# ui_board.net
KiCad netlist of a schematic drawn in EAGLE
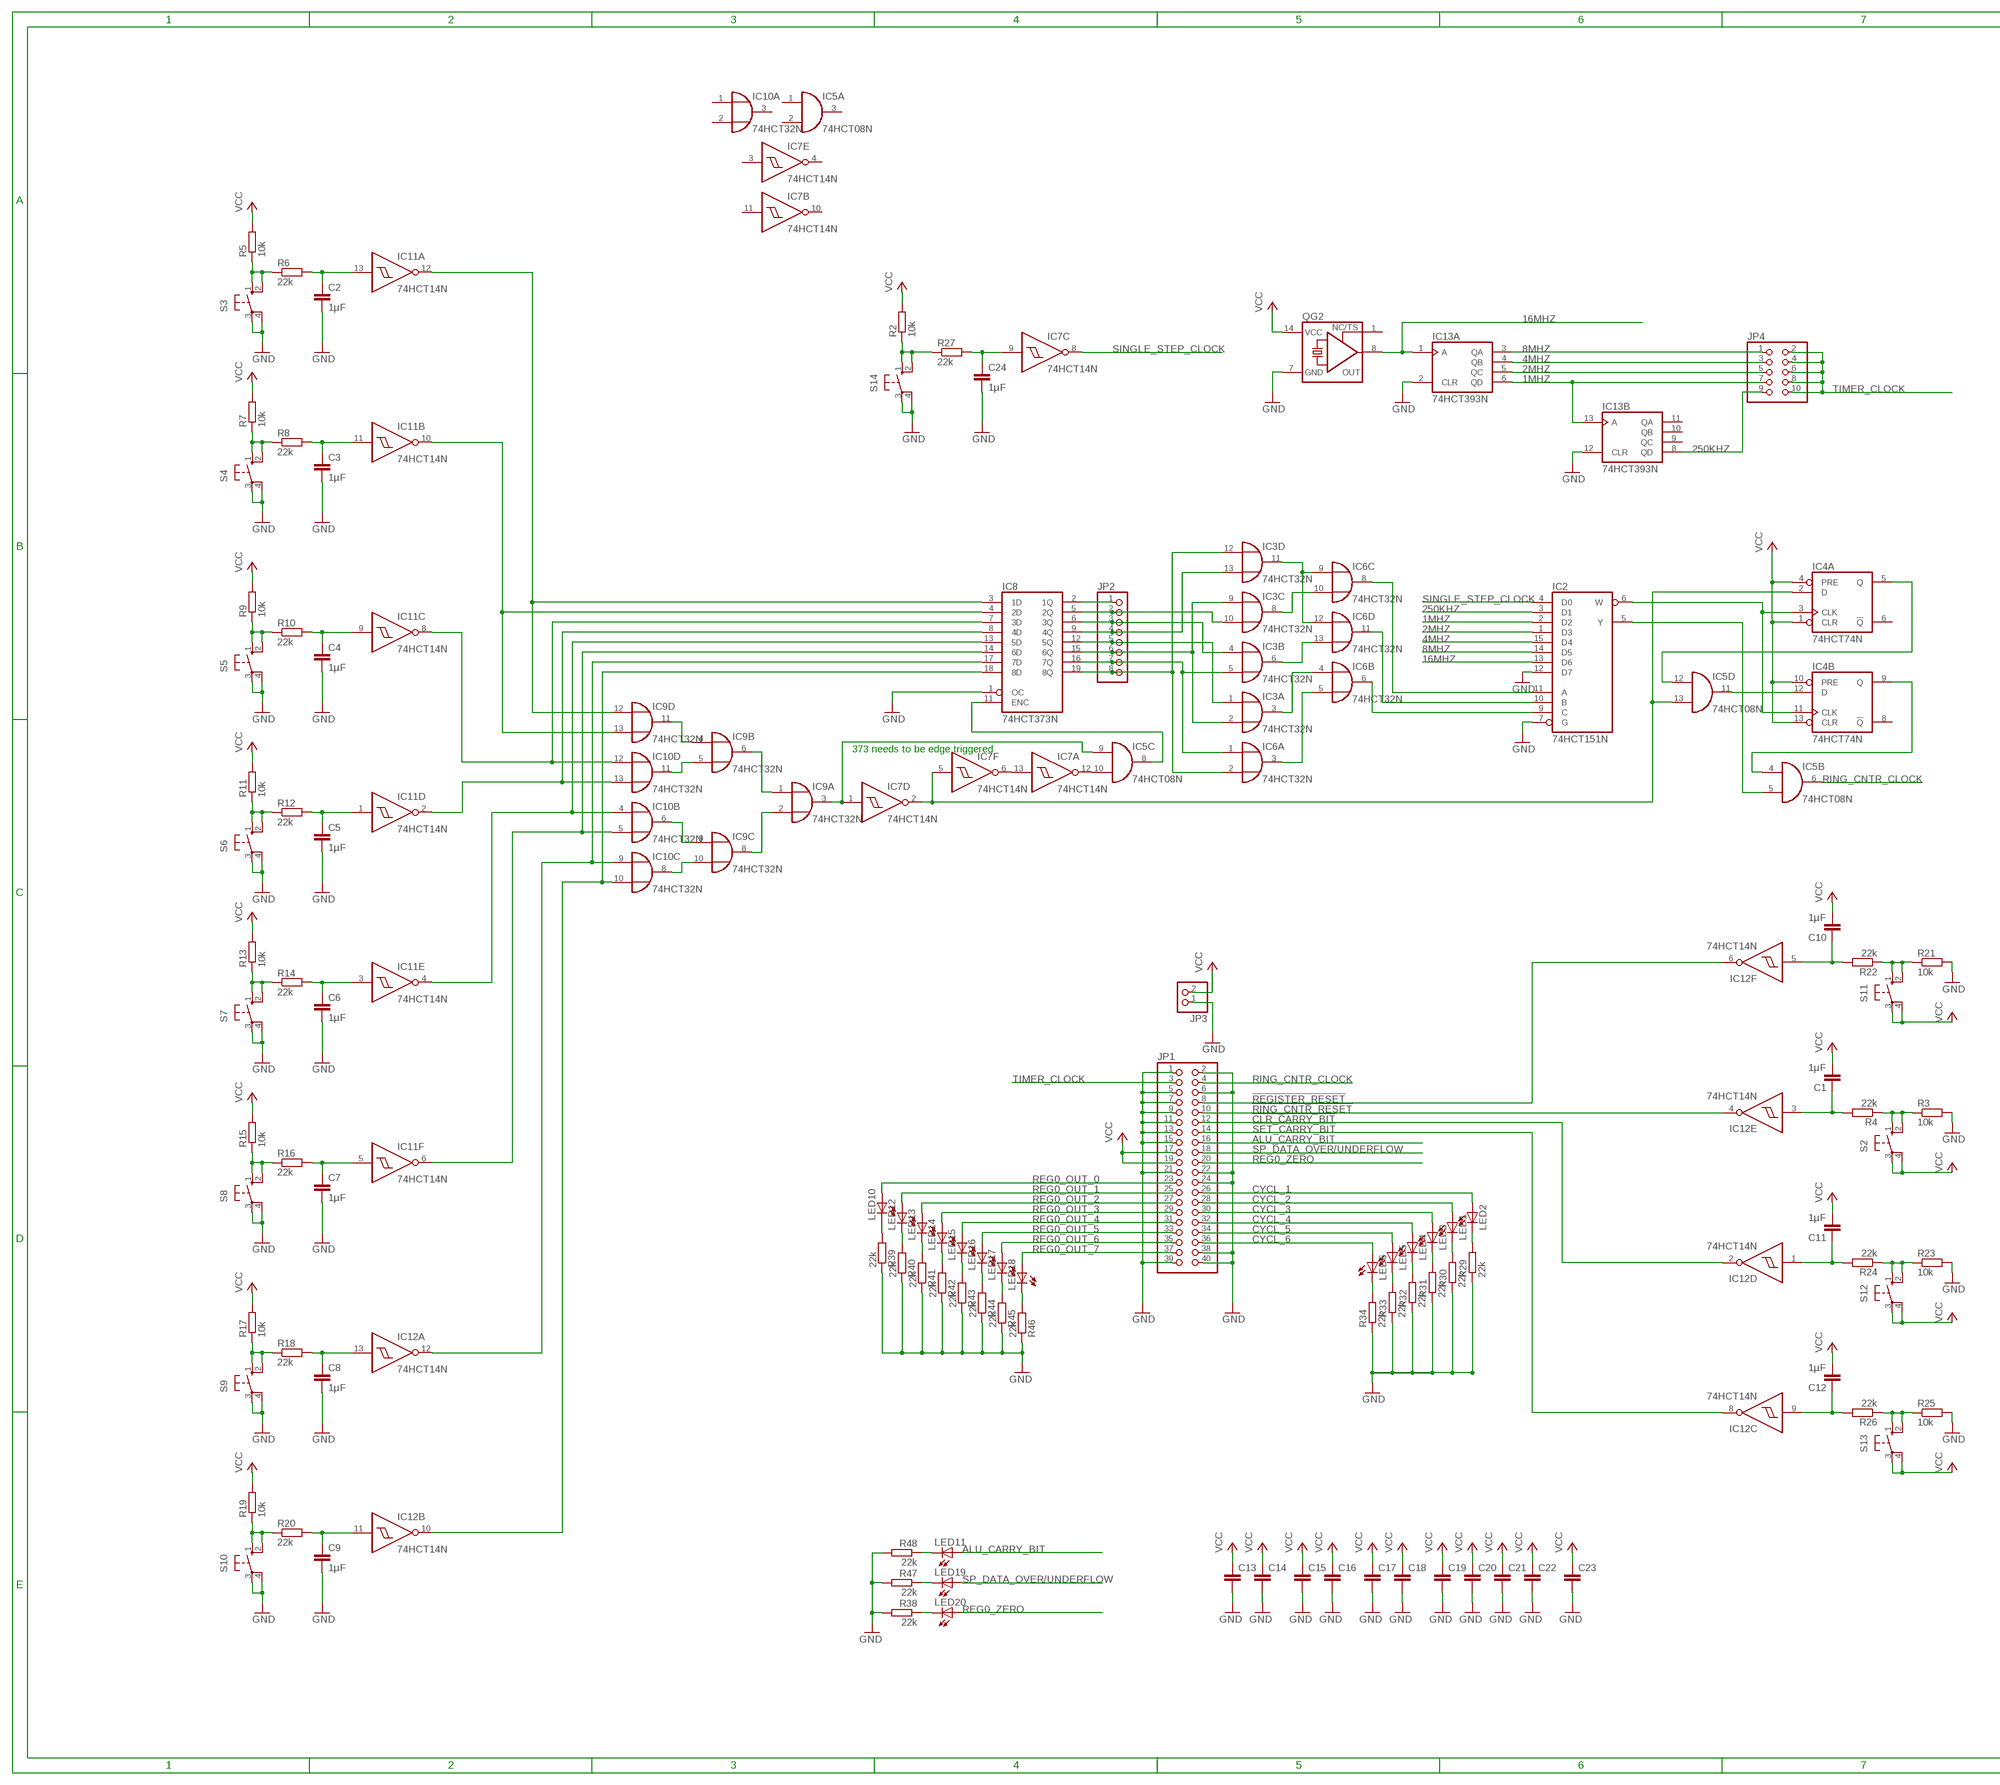
[diagram p0: schematic, sheet 1, part 1 of 2]
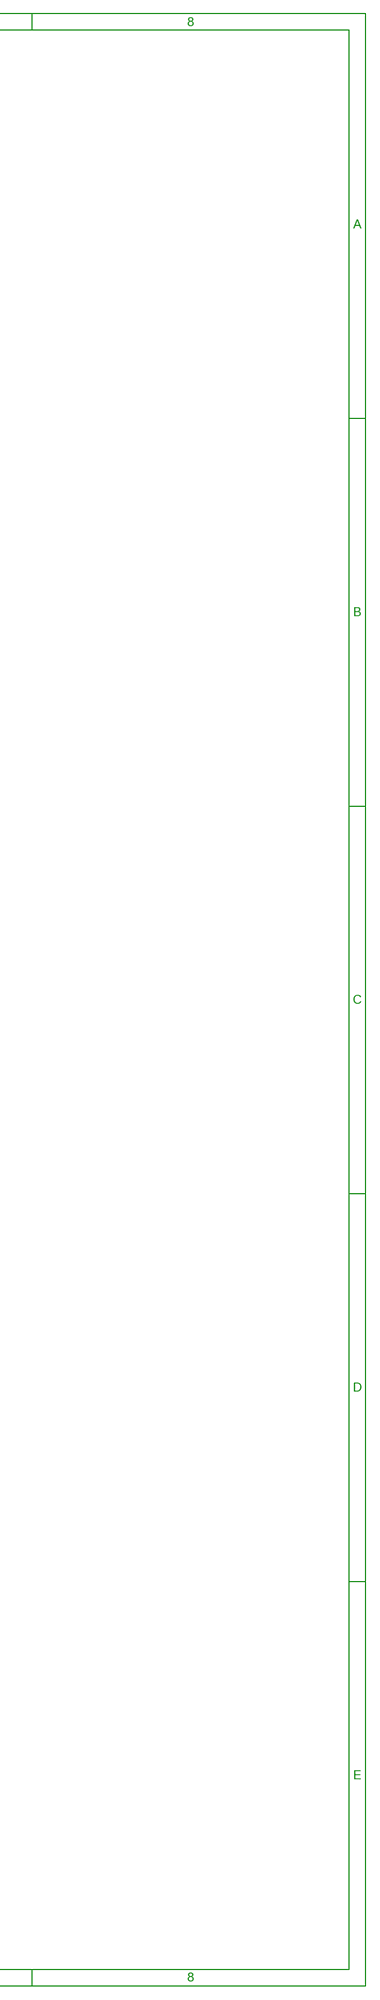
[diagram p1: schematic, sheet 1, part 2 of 2]

(export (version "E")
  (design (tool "Eeschema 10.0.6"))
  (components
    (comp (ref "C1")
      (value "1µF")
      (footprint "eagle-import:C025-024X044")
      (libsource (lib "eagle-import") (part "C-EU025-024X044"))
    )
    (comp (ref "C2")
      (value "1µF")
      (footprint "eagle-import:C025-024X044")
      (libsource (lib "eagle-import") (part "C-EU025-024X044"))
    )
    (comp (ref "C3")
      (value "1µF")
      (footprint "eagle-import:C025-024X044")
      (libsource (lib "eagle-import") (part "C-EU025-024X044"))
    )
    (comp (ref "C4")
      (value "1µF")
      (footprint "eagle-import:C025-024X044")
      (libsource (lib "eagle-import") (part "C-EU025-024X044"))
    )
    (comp (ref "C5")
      (value "1µF")
      (footprint "eagle-import:C025-024X044")
      (libsource (lib "eagle-import") (part "C-EU025-024X044"))
    )
    (comp (ref "C6")
      (value "1µF")
      (footprint "eagle-import:C025-024X044")
      (libsource (lib "eagle-import") (part "C-EU025-024X044"))
    )
    (comp (ref "C7")
      (value "1µF")
      (footprint "eagle-import:C025-024X044")
      (libsource (lib "eagle-import") (part "C-EU025-024X044"))
    )
    (comp (ref "C8")
      (value "1µF")
      (footprint "eagle-import:C025-024X044")
      (libsource (lib "eagle-import") (part "C-EU025-024X044"))
    )
    (comp (ref "C9")
      (value "1µF")
      (footprint "eagle-import:C025-024X044")
      (libsource (lib "eagle-import") (part "C-EU025-024X044"))
    )
    (comp (ref "C10")
      (value "1µF")
      (footprint "eagle-import:C025-024X044")
      (libsource (lib "eagle-import") (part "C-EU025-024X044"))
    )
    (comp (ref "C11")
      (value "1µF")
      (footprint "eagle-import:C025-024X044")
      (libsource (lib "eagle-import") (part "C-EU025-024X044"))
    )
    (comp (ref "C12")
      (value "1µF")
      (footprint "eagle-import:C025-024X044")
      (libsource (lib "eagle-import") (part "C-EU025-024X044"))
    )
    (comp (ref "C13")
      (value "C-EUC1206")
      (footprint "eagle-import:C1206")
      (libsource (lib "eagle-import") (part "C-EUC1206"))
    )
    (comp (ref "C14")
      (value "C-EUC1206")
      (footprint "eagle-import:C1206")
      (libsource (lib "eagle-import") (part "C-EUC1206"))
    )
    (comp (ref "C15")
      (value "C-EUC1206")
      (footprint "eagle-import:C1206")
      (libsource (lib "eagle-import") (part "C-EUC1206"))
    )
    (comp (ref "C16")
      (value "C-EUC1206")
      (footprint "eagle-import:C1206")
      (libsource (lib "eagle-import") (part "C-EUC1206"))
    )
    (comp (ref "C17")
      (value "C-EUC1206")
      (footprint "eagle-import:C1206")
      (libsource (lib "eagle-import") (part "C-EUC1206"))
    )
    (comp (ref "C18")
      (value "C-EUC1206")
      (footprint "eagle-import:C1206")
      (libsource (lib "eagle-import") (part "C-EUC1206"))
    )
    (comp (ref "C19")
      (value "C-EUC1206")
      (footprint "eagle-import:C1206")
      (libsource (lib "eagle-import") (part "C-EUC1206"))
    )
    (comp (ref "C20")
      (value "C-EUC1206")
      (footprint "eagle-import:C1206")
      (libsource (lib "eagle-import") (part "C-EUC1206"))
    )
    (comp (ref "C21")
      (value "C-EUC1206")
      (footprint "eagle-import:C1206")
      (libsource (lib "eagle-import") (part "C-EUC1206"))
    )
    (comp (ref "C22")
      (value "C-EUC1206")
      (footprint "eagle-import:C1206")
      (libsource (lib "eagle-import") (part "C-EUC1206"))
    )
    (comp (ref "C23")
      (value "C-EUC1206")
      (footprint "eagle-import:C1206")
      (libsource (lib "eagle-import") (part "C-EUC1206"))
    )
    (comp (ref "C24")
      (value "1µF")
      (footprint "eagle-import:C025-024X044")
      (libsource (lib "eagle-import") (part "C-EU025-024X044"))
    )
    (comp (ref "IC2")
      (value "74HCT151N")
      (footprint "eagle-import:DIL16")
      (libsource (lib "eagle-import") (part "74151NHCT"))
    )
    (comp (ref "IC3")
      (value "74HCT32N")
      (footprint "eagle-import:DIL14")
      (libsource (lib "eagle-import") (part "7432NHCT"))
    )
    (comp (ref "IC4")
      (value "74HCT74N")
      (footprint "eagle-import:DIL14")
      (libsource (lib "eagle-import") (part "7474NHCT"))
    )
    (comp (ref "IC5")
      (value "74HCT08N")
      (footprint "eagle-import:DIL14")
      (libsource (lib "eagle-import") (part "7408NHCT"))
    )
    (comp (ref "IC6")
      (value "74HCT32N")
      (footprint "eagle-import:DIL14")
      (libsource (lib "eagle-import") (part "7432NHCT"))
    )
    (comp (ref "IC7")
      (value "74HCT14N")
      (footprint "eagle-import:DIL14")
      (libsource (lib "eagle-import") (part "7414NHCT"))
    )
    (comp (ref "IC8")
      (value "74HCT373N")
      (footprint "eagle-import:DIL20")
      (libsource (lib "eagle-import") (part "74373NHCT"))
    )
    (comp (ref "IC9")
      (value "74HCT32N")
      (footprint "eagle-import:DIL14")
      (libsource (lib "eagle-import") (part "7432NHCT"))
    )
    (comp (ref "IC10")
      (value "74HCT32N")
      (footprint "eagle-import:DIL14")
      (libsource (lib "eagle-import") (part "7432NHCT"))
    )
    (comp (ref "IC11")
      (value "74HCT14N")
      (footprint "eagle-import:DIL14")
      (libsource (lib "eagle-import") (part "7414NHCT"))
    )
    (comp (ref "IC12")
      (value "74HCT14N")
      (footprint "eagle-import:DIL14")
      (libsource (lib "eagle-import") (part "7414NHCT"))
    )
    (comp (ref "IC13")
      (value "74HCT393N")
      (footprint "eagle-import:DIL14")
      (libsource (lib "eagle-import") (part "74393NHCT"))
    )
    (comp (ref "JP1")
      (value "PINHD-2X20")
      (footprint "eagle-import:2X20")
      (libsource (lib "eagle-import") (part "PINHD-2X20"))
    )
    (comp (ref "JP2")
      (value "PINHD-1X8")
      (footprint "eagle-import:1X08")
      (libsource (lib "eagle-import") (part "PINHD-1X8"))
    )
    (comp (ref "JP3")
      (value "PINHD-1X2")
      (footprint "eagle-import:1X02")
      (libsource (lib "eagle-import") (part "PINHD-1X2"))
    )
    (comp (ref "JP4")
      (value "PINHD-2X5")
      (footprint "eagle-import:2X05")
      (libsource (lib "eagle-import") (part "PINHD-2X5"))
    )
    (comp (ref "LED1")
      (value "LED3MM")
      (footprint "eagle-import:LED3MM")
      (libsource (lib "eagle-import") (part "LED3MM"))
    )
    (comp (ref "LED2")
      (value "LED3MM")
      (footprint "eagle-import:LED3MM")
      (libsource (lib "eagle-import") (part "LED3MM"))
    )
    (comp (ref "LED3")
      (value "LED3MM")
      (footprint "eagle-import:LED3MM")
      (libsource (lib "eagle-import") (part "LED3MM"))
    )
    (comp (ref "LED4")
      (value "LED3MM")
      (footprint "eagle-import:LED3MM")
      (libsource (lib "eagle-import") (part "LED3MM"))
    )
    (comp (ref "LED5")
      (value "LED3MM")
      (footprint "eagle-import:LED3MM")
      (libsource (lib "eagle-import") (part "LED3MM"))
    )
    (comp (ref "LED6")
      (value "LED3MM")
      (footprint "eagle-import:LED3MM")
      (libsource (lib "eagle-import") (part "LED3MM"))
    )
    (comp (ref "LED10")
      (value "LED3MM")
      (footprint "eagle-import:LED3MM")
      (libsource (lib "eagle-import") (part "LED3MM"))
    )
    (comp (ref "LED11")
      (value "LED3MM")
      (footprint "eagle-import:LED3MM")
      (libsource (lib "eagle-import") (part "LED3MM"))
    )
    (comp (ref "LED12")
      (value "LED3MM")
      (footprint "eagle-import:LED3MM")
      (libsource (lib "eagle-import") (part "LED3MM"))
    )
    (comp (ref "LED13")
      (value "LED3MM")
      (footprint "eagle-import:LED3MM")
      (libsource (lib "eagle-import") (part "LED3MM"))
    )
    (comp (ref "LED14")
      (value "LED3MM")
      (footprint "eagle-import:LED3MM")
      (libsource (lib "eagle-import") (part "LED3MM"))
    )
    (comp (ref "LED15")
      (value "LED3MM")
      (footprint "eagle-import:LED3MM")
      (libsource (lib "eagle-import") (part "LED3MM"))
    )
    (comp (ref "LED16")
      (value "LED3MM")
      (footprint "eagle-import:LED3MM")
      (libsource (lib "eagle-import") (part "LED3MM"))
    )
    (comp (ref "LED17")
      (value "LED3MM")
      (footprint "eagle-import:LED3MM")
      (libsource (lib "eagle-import") (part "LED3MM"))
    )
    (comp (ref "LED18")
      (value "LED3MM")
      (footprint "eagle-import:LED3MM")
      (libsource (lib "eagle-import") (part "LED3MM"))
    )
    (comp (ref "LED19")
      (value "LED3MM")
      (footprint "eagle-import:LED3MM")
      (libsource (lib "eagle-import") (part "LED3MM"))
    )
    (comp (ref "LED20")
      (value "LED3MM")
      (footprint "eagle-import:LED3MM")
      (libsource (lib "eagle-import") (part "LED3MM"))
    )
    (comp (ref "QG2")
      (value "XO-14")
      (footprint "eagle-import:DIL14S")
      (libsource (lib "eagle-import") (part "XO-14"))
    )
    (comp (ref "R2")
      (value "10k")
      (footprint "eagle-import:R1206")
      (libsource (lib "eagle-import") (part "R-EU_R1206"))
    )
    (comp (ref "R3")
      (value "10k")
      (footprint "eagle-import:R1206")
      (libsource (lib "eagle-import") (part "R-EU_R1206"))
    )
    (comp (ref "R4")
      (value "22k")
      (footprint "eagle-import:R1206")
      (libsource (lib "eagle-import") (part "R-EU_R1206"))
    )
    (comp (ref "R5")
      (value "10k")
      (footprint "eagle-import:R1206")
      (libsource (lib "eagle-import") (part "R-EU_R1206"))
    )
    (comp (ref "R6")
      (value "22k")
      (footprint "eagle-import:R1206")
      (libsource (lib "eagle-import") (part "R-EU_R1206"))
    )
    (comp (ref "R7")
      (value "10k")
      (footprint "eagle-import:R1206")
      (libsource (lib "eagle-import") (part "R-EU_R1206"))
    )
    (comp (ref "R8")
      (value "22k")
      (footprint "eagle-import:R1206")
      (libsource (lib "eagle-import") (part "R-EU_R1206"))
    )
    (comp (ref "R9")
      (value "10k")
      (footprint "eagle-import:R1206")
      (libsource (lib "eagle-import") (part "R-EU_R1206"))
    )
    (comp (ref "R10")
      (value "22k")
      (footprint "eagle-import:R1206")
      (libsource (lib "eagle-import") (part "R-EU_R1206"))
    )
    (comp (ref "R11")
      (value "10k")
      (footprint "eagle-import:R1206")
      (libsource (lib "eagle-import") (part "R-EU_R1206"))
    )
    (comp (ref "R12")
      (value "22k")
      (footprint "eagle-import:R1206")
      (libsource (lib "eagle-import") (part "R-EU_R1206"))
    )
    (comp (ref "R13")
      (value "10k")
      (footprint "eagle-import:R1206")
      (libsource (lib "eagle-import") (part "R-EU_R1206"))
    )
    (comp (ref "R14")
      (value "22k")
      (footprint "eagle-import:R1206")
      (libsource (lib "eagle-import") (part "R-EU_R1206"))
    )
    (comp (ref "R15")
      (value "10k")
      (footprint "eagle-import:R1206")
      (libsource (lib "eagle-import") (part "R-EU_R1206"))
    )
    (comp (ref "R16")
      (value "22k")
      (footprint "eagle-import:R1206")
      (libsource (lib "eagle-import") (part "R-EU_R1206"))
    )
    (comp (ref "R17")
      (value "10k")
      (footprint "eagle-import:R1206")
      (libsource (lib "eagle-import") (part "R-EU_R1206"))
    )
    (comp (ref "R18")
      (value "22k")
      (footprint "eagle-import:R1206")
      (libsource (lib "eagle-import") (part "R-EU_R1206"))
    )
    (comp (ref "R19")
      (value "10k")
      (footprint "eagle-import:R1206")
      (libsource (lib "eagle-import") (part "R-EU_R1206"))
    )
    (comp (ref "R20")
      (value "22k")
      (footprint "eagle-import:R1206")
      (libsource (lib "eagle-import") (part "R-EU_R1206"))
    )
    (comp (ref "R21")
      (value "10k")
      (footprint "eagle-import:R1206")
      (libsource (lib "eagle-import") (part "R-EU_R1206"))
    )
    (comp (ref "R22")
      (value "22k")
      (footprint "eagle-import:R1206")
      (libsource (lib "eagle-import") (part "R-EU_R1206"))
    )
    (comp (ref "R23")
      (value "10k")
      (footprint "eagle-import:R1206")
      (libsource (lib "eagle-import") (part "R-EU_R1206"))
    )
    (comp (ref "R24")
      (value "22k")
      (footprint "eagle-import:R1206")
      (libsource (lib "eagle-import") (part "R-EU_R1206"))
    )
    (comp (ref "R25")
      (value "10k")
      (footprint "eagle-import:R1206")
      (libsource (lib "eagle-import") (part "R-EU_R1206"))
    )
    (comp (ref "R26")
      (value "22k")
      (footprint "eagle-import:R1206")
      (libsource (lib "eagle-import") (part "R-EU_R1206"))
    )
    (comp (ref "R27")
      (value "22k")
      (footprint "eagle-import:R1206")
      (libsource (lib "eagle-import") (part "R-EU_R1206"))
    )
    (comp (ref "R29")
      (value "22k")
      (footprint "eagle-import:R1206")
      (libsource (lib "eagle-import") (part "R-EU_R1206"))
    )
    (comp (ref "R30")
      (value "22k")
      (footprint "eagle-import:R1206")
      (libsource (lib "eagle-import") (part "R-EU_R1206"))
    )
    (comp (ref "R31")
      (value "22k")
      (footprint "eagle-import:R1206")
      (libsource (lib "eagle-import") (part "R-EU_R1206"))
    )
    (comp (ref "R32")
      (value "22k")
      (footprint "eagle-import:R1206")
      (libsource (lib "eagle-import") (part "R-EU_R1206"))
    )
    (comp (ref "R33")
      (value "22k")
      (footprint "eagle-import:R1206")
      (libsource (lib "eagle-import") (part "R-EU_R1206"))
    )
    (comp (ref "R34")
      (value "22k")
      (footprint "eagle-import:R1206")
      (libsource (lib "eagle-import") (part "R-EU_R1206"))
    )
    (comp (ref "R38")
      (value "22k")
      (footprint "eagle-import:R1206")
      (libsource (lib "eagle-import") (part "R-EU_R1206"))
    )
    (comp (ref "R39")
      (value "22k")
      (footprint "eagle-import:R1206")
      (libsource (lib "eagle-import") (part "R-EU_R1206"))
    )
    (comp (ref "R40")
      (value "22k")
      (footprint "eagle-import:R1206")
      (libsource (lib "eagle-import") (part "R-EU_R1206"))
    )
    (comp (ref "R41")
      (value "22k")
      (footprint "eagle-import:R1206")
      (libsource (lib "eagle-import") (part "R-EU_R1206"))
    )
    (comp (ref "R42")
      (value "22k")
      (footprint "eagle-import:R1206")
      (libsource (lib "eagle-import") (part "R-EU_R1206"))
    )
    (comp (ref "R43")
      (value "22k")
      (footprint "eagle-import:R1206")
      (libsource (lib "eagle-import") (part "R-EU_R1206"))
    )
    (comp (ref "R44")
      (value "22k")
      (footprint "eagle-import:R1206")
      (libsource (lib "eagle-import") (part "R-EU_R1206"))
    )
    (comp (ref "R45")
      (value "22k")
      (footprint "eagle-import:R1206")
      (libsource (lib "eagle-import") (part "R-EU_R1206"))
    )
    (comp (ref "R46")
      (value "22k")
      (footprint "eagle-import:R1206")
      (libsource (lib "eagle-import") (part "R-EU_R1206"))
    )
    (comp (ref "R47")
      (value "22k")
      (footprint "eagle-import:R1206")
      (libsource (lib "eagle-import") (part "R-EU_R1206"))
    )
    (comp (ref "R48")
      (value "22k")
      (footprint "eagle-import:R1206")
      (libsource (lib "eagle-import") (part "R-EU_R1206"))
    )
    (comp (ref "S2")
      (value "10-XX")
      (footprint "eagle-import:B3F-10XX")
      (fields (field (name "MPN") "B3F-1000"))
      (libsource (lib "eagle-import") (part "10-XX"))
    )
    (comp (ref "S3")
      (value "10-XX")
      (footprint "eagle-import:B3F-10XX")
      (fields (field (name "MPN") "B3F-1000"))
      (libsource (lib "eagle-import") (part "10-XX"))
    )
    (comp (ref "S4")
      (value "10-XX")
      (footprint "eagle-import:B3F-10XX")
      (fields (field (name "MPN") "B3F-1000"))
      (libsource (lib "eagle-import") (part "10-XX"))
    )
    (comp (ref "S5")
      (value "10-XX")
      (footprint "eagle-import:B3F-10XX")
      (fields (field (name "MPN") "B3F-1000"))
      (libsource (lib "eagle-import") (part "10-XX"))
    )
    (comp (ref "S6")
      (value "10-XX")
      (footprint "eagle-import:B3F-10XX")
      (fields (field (name "MPN") "B3F-1000"))
      (libsource (lib "eagle-import") (part "10-XX"))
    )
    (comp (ref "S7")
      (value "10-XX")
      (footprint "eagle-import:B3F-10XX")
      (fields (field (name "MPN") "B3F-1000"))
      (libsource (lib "eagle-import") (part "10-XX"))
    )
    (comp (ref "S8")
      (value "10-XX")
      (footprint "eagle-import:B3F-10XX")
      (fields (field (name "MPN") "B3F-1000"))
      (libsource (lib "eagle-import") (part "10-XX"))
    )
    (comp (ref "S9")
      (value "10-XX")
      (footprint "eagle-import:B3F-10XX")
      (fields (field (name "MPN") "B3F-1000"))
      (libsource (lib "eagle-import") (part "10-XX"))
    )
    (comp (ref "S10")
      (value "10-XX")
      (footprint "eagle-import:B3F-10XX")
      (fields (field (name "MPN") "B3F-1000"))
      (libsource (lib "eagle-import") (part "10-XX"))
    )
    (comp (ref "S11")
      (value "10-XX")
      (footprint "eagle-import:B3F-10XX")
      (fields (field (name "MPN") "B3F-1000"))
      (libsource (lib "eagle-import") (part "10-XX"))
    )
    (comp (ref "S12")
      (value "10-XX")
      (footprint "eagle-import:B3F-10XX")
      (fields (field (name "MPN") "B3F-1000"))
      (libsource (lib "eagle-import") (part "10-XX"))
    )
    (comp (ref "S13")
      (value "10-XX")
      (footprint "eagle-import:B3F-10XX")
      (fields (field (name "MPN") "B3F-1000"))
      (libsource (lib "eagle-import") (part "10-XX"))
    )
    (comp (ref "S14")
      (value "10-XX")
      (footprint "eagle-import:B3F-10XX")
      (fields (field (name "MPN") "B3F-1000"))
      (libsource (lib "eagle-import") (part "10-XX"))
    )
  )
  (nets
    (net (code "1") (name "/1MHZ") (class "Default")
      (node (ref "IC13") (pin "13") (pinfunction "A_13") (pintype "input"))
      (node (ref "IC13") (pin "6") (pinfunction "QD_6") (pintype "output"))
      (node (ref "IC2") (pin "2") (pinfunction "D2_2") (pintype "input"))
      (node (ref "JP4") (pin "7") (pinfunction "7_7") (pintype "passive"))
    )
    (net (code "2") (name "/2MHZ") (class "Default")
      (node (ref "IC13") (pin "5") (pinfunction "QC_5") (pintype "output"))
      (node (ref "IC2") (pin "1") (pinfunction "D3_1") (pintype "input"))
      (node (ref "JP4") (pin "5") (pinfunction "5_5") (pintype "passive"))
    )
    (net (code "3") (name "/4MHZ") (class "Default")
      (node (ref "IC13") (pin "4") (pinfunction "QB_4") (pintype "output"))
      (node (ref "IC2") (pin "15") (pinfunction "D4_15") (pintype "input"))
      (node (ref "JP4") (pin "3") (pinfunction "3_3") (pintype "passive"))
    )
    (net (code "4") (name "/8MHZ") (class "Default")
      (node (ref "IC13") (pin "3") (pinfunction "QA_3") (pintype "output"))
      (node (ref "IC2") (pin "14") (pinfunction "D5_14") (pintype "input"))
      (node (ref "JP4") (pin "1") (pinfunction "1_1") (pintype "passive"))
    )
    (net (code "5") (name "/16MHZ") (class "Default")
      (node (ref "IC13") (pin "1") (pinfunction "A_1") (pintype "input"))
      (node (ref "IC2") (pin "13") (pinfunction "D6_13") (pintype "input"))
      (node (ref "QG2") (pin "8") (pinfunction "OUT_8") (pintype "output"))
    )
    (net (code "6") (name "/250KHZ") (class "Default")
      (node (ref "IC13") (pin "8") (pinfunction "QD_8") (pintype "output"))
      (node (ref "IC2") (pin "3") (pinfunction "D1_3") (pintype "input"))
      (node (ref "JP4") (pin "9") (pinfunction "9_9") (pintype "passive"))
    )
    (net (code "7") (name "/ALU_CARRY_BIT") (class "Default")
      (node (ref "JP1") (pin "16") (pinfunction "16_16") (pintype "passive"))
      (node (ref "LED11") (pin "A") (pinfunction "A_A") (pintype "passive"))
    )
    (net (code "8") (name "/CYCL_1") (class "Default")
      (node (ref "JP1") (pin "26") (pinfunction "26_26") (pintype "passive"))
      (node (ref "LED2") (pin "A") (pinfunction "A_A") (pintype "passive"))
    )
    (net (code "9") (name "/CYCL_2") (class "Default")
      (node (ref "JP1") (pin "28") (pinfunction "28_28") (pintype "passive"))
      (node (ref "LED1") (pin "A") (pinfunction "A_A") (pintype "passive"))
    )
    (net (code "10") (name "/CYCL_3") (class "Default")
      (node (ref "JP1") (pin "30") (pinfunction "30_30") (pintype "passive"))
      (node (ref "LED3") (pin "A") (pinfunction "A_A") (pintype "passive"))
    )
    (net (code "11") (name "/CYCL_4") (class "Default")
      (node (ref "JP1") (pin "32") (pinfunction "32_32") (pintype "passive"))
      (node (ref "LED4") (pin "A") (pinfunction "A_A") (pintype "passive"))
    )
    (net (code "12") (name "/CYCL_5") (class "Default")
      (node (ref "JP1") (pin "34") (pinfunction "34_34") (pintype "passive"))
      (node (ref "LED5") (pin "A") (pinfunction "A_A") (pintype "passive"))
    )
    (net (code "13") (name "/CYCL_6") (class "Default")
      (node (ref "JP1") (pin "36") (pinfunction "36_36") (pintype "passive"))
      (node (ref "LED6") (pin "A") (pinfunction "A_A") (pintype "passive"))
    )
    (net (code "14") (name "/REG0_OUT_0") (class "Default")
      (node (ref "JP1") (pin "23") (pinfunction "23_23") (pintype "passive"))
      (node (ref "LED10") (pin "A") (pinfunction "A_A") (pintype "passive"))
    )
    (net (code "15") (name "/REG0_OUT_1") (class "Default")
      (node (ref "JP1") (pin "25") (pinfunction "25_25") (pintype "passive"))
      (node (ref "LED12") (pin "A") (pinfunction "A_A") (pintype "passive"))
    )
    (net (code "16") (name "/REG0_OUT_2") (class "Default")
      (node (ref "JP1") (pin "27") (pinfunction "27_27") (pintype "passive"))
      (node (ref "LED13") (pin "A") (pinfunction "A_A") (pintype "passive"))
    )
    (net (code "17") (name "/REG0_OUT_3") (class "Default")
      (node (ref "JP1") (pin "29") (pinfunction "29_29") (pintype "passive"))
      (node (ref "LED14") (pin "A") (pinfunction "A_A") (pintype "passive"))
    )
    (net (code "18") (name "/REG0_OUT_4") (class "Default")
      (node (ref "JP1") (pin "31") (pinfunction "31_31") (pintype "passive"))
      (node (ref "LED15") (pin "A") (pinfunction "A_A") (pintype "passive"))
    )
    (net (code "19") (name "/REG0_OUT_5") (class "Default")
      (node (ref "JP1") (pin "33") (pinfunction "33_33") (pintype "passive"))
      (node (ref "LED16") (pin "A") (pinfunction "A_A") (pintype "passive"))
    )
    (net (code "20") (name "/REG0_OUT_6") (class "Default")
      (node (ref "JP1") (pin "35") (pinfunction "35_35") (pintype "passive"))
      (node (ref "LED17") (pin "A") (pinfunction "A_A") (pintype "passive"))
    )
    (net (code "21") (name "/REG0_OUT_7") (class "Default")
      (node (ref "JP1") (pin "37") (pinfunction "37_37") (pintype "passive"))
      (node (ref "LED18") (pin "A") (pinfunction "A_A") (pintype "passive"))
    )
    (net (code "22") (name "/REG0_ZERO") (class "Default")
      (node (ref "JP1") (pin "20") (pinfunction "20_20") (pintype "passive"))
      (node (ref "LED20") (pin "A") (pinfunction "A_A") (pintype "passive"))
    )
    (net (code "23") (name "/RING_CNTR_CLOCK") (class "Default")
      (node (ref "IC5") (pin "6") (pinfunction "O_6") (pintype "output"))
      (node (ref "JP1") (pin "4") (pinfunction "4_4") (pintype "passive"))
    )
    (net (code "24") (name "/SINGLE_STEP_CLOCK") (class "Default")
      (node (ref "IC2") (pin "4") (pinfunction "D0_4") (pintype "input"))
      (node (ref "IC7") (pin "8") (pinfunction "O_8") (pintype "output"))
    )
    (net (code "25") (name "/SP_DATA_OVER{slash}UNDERFLOW") (class "Default")
      (node (ref "JP1") (pin "18") (pinfunction "18_18") (pintype "passive"))
      (node (ref "LED19") (pin "A") (pinfunction "A_A") (pintype "passive"))
    )
    (net (code "26") (name "/TIMER_CLOCK") (class "Default")
      (node (ref "JP1") (pin "3") (pinfunction "3_3") (pintype "passive"))
      (node (ref "JP4") (pin "10") (pinfunction "10_10") (pintype "passive"))
      (node (ref "JP4") (pin "2") (pinfunction "2_2") (pintype "passive"))
      (node (ref "JP4") (pin "4") (pinfunction "4_4") (pintype "passive"))
      (node (ref "JP4") (pin "6") (pinfunction "6_6") (pintype "passive"))
      (node (ref "JP4") (pin "8") (pinfunction "8_8") (pintype "passive"))
    )
    (net (code "27") (name "/~{CLR_CARRY_BIT}") (class "Default")
      (node (ref "IC12") (pin "2") (pinfunction "O_2") (pintype "output"))
      (node (ref "JP1") (pin "12") (pinfunction "12_12") (pintype "passive"))
    )
    (net (code "28") (name "/~{REGISTER_RESET}") (class "Default")
      (node (ref "IC12") (pin "6") (pinfunction "O_6") (pintype "output"))
      (node (ref "JP1") (pin "8") (pinfunction "8_8") (pintype "passive"))
    )
    (net (code "29") (name "/~{RING_CNTR_RESET}") (class "Default")
      (node (ref "IC12") (pin "4") (pinfunction "O_4") (pintype "output"))
      (node (ref "JP1") (pin "10") (pinfunction "10_10") (pintype "passive"))
    )
    (net (code "30") (name "/~{SET_CARRY_BIT}") (class "Default")
      (node (ref "IC12") (pin "8") (pinfunction "O_8") (pintype "output"))
      (node (ref "JP1") (pin "14") (pinfunction "14_14") (pintype "passive"))
    )
    (net (code "31") (name "GND") (class "Default")
      (node (ref "C13") (pin "2") (pinfunction "2_2") (pintype "passive"))
      (node (ref "C14") (pin "2") (pinfunction "2_2") (pintype "passive"))
      (node (ref "C15") (pin "2") (pinfunction "2_2") (pintype "passive"))
      (node (ref "C16") (pin "2") (pinfunction "2_2") (pintype "passive"))
      (node (ref "C17") (pin "2") (pinfunction "2_2") (pintype "passive"))
      (node (ref "C18") (pin "2") (pinfunction "2_2") (pintype "passive"))
      (node (ref "C19") (pin "2") (pinfunction "2_2") (pintype "passive"))
      (node (ref "C2") (pin "2") (pinfunction "2_2") (pintype "passive"))
      (node (ref "C20") (pin "2") (pinfunction "2_2") (pintype "passive"))
      (node (ref "C21") (pin "2") (pinfunction "2_2") (pintype "passive"))
      (node (ref "C22") (pin "2") (pinfunction "2_2") (pintype "passive"))
      (node (ref "C23") (pin "2") (pinfunction "2_2") (pintype "passive"))
      (node (ref "C24") (pin "2") (pinfunction "2_2") (pintype "passive"))
      (node (ref "C3") (pin "2") (pinfunction "2_2") (pintype "passive"))
      (node (ref "C4") (pin "2") (pinfunction "2_2") (pintype "passive"))
      (node (ref "C5") (pin "2") (pinfunction "2_2") (pintype "passive"))
      (node (ref "C6") (pin "2") (pinfunction "2_2") (pintype "passive"))
      (node (ref "C7") (pin "2") (pinfunction "2_2") (pintype "passive"))
      (node (ref "C8") (pin "2") (pinfunction "2_2") (pintype "passive"))
      (node (ref "C9") (pin "2") (pinfunction "2_2") (pintype "passive"))
      (node (ref "IC13") (pin "12") (pinfunction "CLR_12") (pintype "input"))
      (node (ref "IC13") (pin "2") (pinfunction "CLR_2") (pintype "input"))
      (node (ref "IC2") (pin "12") (pinfunction "D7_12") (pintype "input"))
      (node (ref "IC2") (pin "7") (pinfunction "G_7") (pintype "input"))
      (node (ref "IC8") (pin "1") (pinfunction "OC_1") (pintype "input"))
      (node (ref "JP1") (pin "1") (pinfunction "1_1") (pintype "passive"))
      (node (ref "JP1") (pin "11") (pinfunction "11_11") (pintype "passive"))
      (node (ref "JP1") (pin "13") (pinfunction "13_13") (pintype "passive"))
      (node (ref "JP1") (pin "15") (pinfunction "15_15") (pintype "passive"))
      (node (ref "JP1") (pin "2") (pinfunction "2_2") (pintype "passive"))
      (node (ref "JP1") (pin "21") (pinfunction "21_21") (pintype "passive"))
      (node (ref "JP1") (pin "22") (pinfunction "22_22") (pintype "passive"))
      (node (ref "JP1") (pin "24") (pinfunction "24_24") (pintype "passive"))
      (node (ref "JP1") (pin "38") (pinfunction "38_38") (pintype "passive"))
      (node (ref "JP1") (pin "39") (pinfunction "39_39") (pintype "passive"))
      (node (ref "JP1") (pin "40") (pinfunction "40_40") (pintype "passive"))
      (node (ref "JP1") (pin "5") (pinfunction "5_5") (pintype "passive"))
      (node (ref "JP1") (pin "6") (pinfunction "6_6") (pintype "passive"))
      (node (ref "JP1") (pin "7") (pinfunction "7_7") (pintype "passive"))
      (node (ref "JP1") (pin "9") (pinfunction "9_9") (pintype "passive"))
      (node (ref "JP3") (pin "1") (pinfunction "1_1") (pintype "passive"))
      (node (ref "QG2") (pin "7") (pinfunction "GND_7") (pintype "power_in"))
      (node (ref "R21") (pin "2") (pinfunction "2_2") (pintype "passive"))
      (node (ref "R23") (pin "2") (pinfunction "2_2") (pintype "passive"))
      (node (ref "R25") (pin "2") (pinfunction "2_2") (pintype "passive"))
      (node (ref "R29") (pin "1") (pinfunction "1_1") (pintype "passive"))
      (node (ref "R3") (pin "2") (pinfunction "2_2") (pintype "passive"))
      (node (ref "R30") (pin "1") (pinfunction "1_1") (pintype "passive"))
      (node (ref "R31") (pin "1") (pinfunction "1_1") (pintype "passive"))
      (node (ref "R32") (pin "1") (pinfunction "1_1") (pintype "passive"))
      (node (ref "R33") (pin "1") (pinfunction "1_1") (pintype "passive"))
      (node (ref "R34") (pin "1") (pinfunction "1_1") (pintype "passive"))
      (node (ref "R38") (pin "2") (pinfunction "2_2") (pintype "passive"))
      (node (ref "R39") (pin "1") (pinfunction "1_1") (pintype "passive"))
      (node (ref "R40") (pin "1") (pinfunction "1_1") (pintype "passive"))
      (node (ref "R41") (pin "1") (pinfunction "1_1") (pintype "passive"))
      (node (ref "R42") (pin "1") (pinfunction "1_1") (pintype "passive"))
      (node (ref "R43") (pin "1") (pinfunction "1_1") (pintype "passive"))
      (node (ref "R44") (pin "1") (pinfunction "1_1") (pintype "passive"))
      (node (ref "R45") (pin "1") (pinfunction "1_1") (pintype "passive"))
      (node (ref "R46") (pin "1") (pinfunction "1_1") (pintype "passive"))
      (node (ref "R47") (pin "2") (pinfunction "2_2") (pintype "passive"))
      (node (ref "R48") (pin "2") (pinfunction "2_2") (pintype "passive"))
      (node (ref "S10") (pin "3") (pinfunction "P_3") (pintype "passive"))
      (node (ref "S10") (pin "4") (pinfunction "P1_4") (pintype "passive"))
      (node (ref "S14") (pin "3") (pinfunction "P_3") (pintype "passive"))
      (node (ref "S14") (pin "4") (pinfunction "P1_4") (pintype "passive"))
      (node (ref "S3") (pin "3") (pinfunction "P_3") (pintype "passive"))
      (node (ref "S3") (pin "4") (pinfunction "P1_4") (pintype "passive"))
      (node (ref "S4") (pin "3") (pinfunction "P_3") (pintype "passive"))
      (node (ref "S4") (pin "4") (pinfunction "P1_4") (pintype "passive"))
      (node (ref "S5") (pin "3") (pinfunction "P_3") (pintype "passive"))
      (node (ref "S5") (pin "4") (pinfunction "P1_4") (pintype "passive"))
      (node (ref "S6") (pin "3") (pinfunction "P_3") (pintype "passive"))
      (node (ref "S6") (pin "4") (pinfunction "P1_4") (pintype "passive"))
      (node (ref "S7") (pin "3") (pinfunction "P_3") (pintype "passive"))
      (node (ref "S7") (pin "4") (pinfunction "P1_4") (pintype "passive"))
      (node (ref "S8") (pin "3") (pinfunction "P_3") (pintype "passive"))
      (node (ref "S8") (pin "4") (pinfunction "P1_4") (pintype "passive"))
      (node (ref "S9") (pin "3") (pinfunction "P_3") (pintype "passive"))
      (node (ref "S9") (pin "4") (pinfunction "P1_4") (pintype "passive"))
    )
    (net (code "32") (name "Net-(IC2A-A)") (class "Default")
      (node (ref "IC2") (pin "11") (pinfunction "A_11") (pintype "input"))
      (node (ref "IC6") (pin "8") (pinfunction "O_8") (pintype "output"))
    )
    (net (code "33") (name "Net-(IC2A-B)") (class "Default")
      (node (ref "IC2") (pin "10") (pinfunction "B_10") (pintype "input"))
      (node (ref "IC6") (pin "11") (pinfunction "O_11") (pintype "output"))
    )
    (net (code "34") (name "Net-(IC2A-C)") (class "Default")
      (node (ref "IC2") (pin "9") (pinfunction "C_9") (pintype "input"))
      (node (ref "IC6") (pin "6") (pinfunction "O_6") (pintype "output"))
    )
    (net (code "35") (name "Net-(IC2A-W)") (class "Default")
      (node (ref "IC2") (pin "6") (pinfunction "W_6") (pintype "output"))
      (node (ref "IC4") (pin "11") (pinfunction "CLK_11") (pintype "input"))
      (node (ref "IC4") (pin "3") (pinfunction "CLK_3") (pintype "input"))
    )
    (net (code "36") (name "Net-(IC2A-Y)") (class "Default")
      (node (ref "IC2") (pin "5") (pinfunction "Y_5") (pintype "output"))
      (node (ref "IC5") (pin "5") (pinfunction "I1_5") (pintype "input"))
    )
    (net (code "37") (name "Net-(IC3A-I0)") (class "Default")
      (node (ref "IC3") (pin "1") (pinfunction "I0_1") (pintype "input"))
      (node (ref "IC8") (pin "12") (pinfunction "5Q_12") (pintype "tri_state"))
      (node (ref "JP2") (pin "5") (pinfunction "5_5") (pintype "passive"))
    )
    (net (code "38") (name "Net-(IC3A-I1)") (class "Default")
      (node (ref "IC3") (pin "2") (pinfunction "I1_2") (pintype "input"))
      (node (ref "IC3") (pin "9") (pinfunction "I0_9") (pintype "input"))
      (node (ref "IC8") (pin "15") (pinfunction "6Q_15") (pintype "tri_state"))
      (node (ref "JP2") (pin "6") (pinfunction "6_6") (pintype "passive"))
    )
    (net (code "39") (name "Net-(IC3A-O)") (class "Default")
      (node (ref "IC3") (pin "3") (pinfunction "O_3") (pintype "output"))
      (node (ref "IC6") (pin "4") (pinfunction "I0_4") (pintype "input"))
    )
    (net (code "40") (name "Net-(IC3B-I0)") (class "Default")
      (node (ref "IC3") (pin "4") (pinfunction "I0_4") (pintype "input"))
      (node (ref "IC8") (pin "6") (pinfunction "3Q_6") (pintype "tri_state"))
      (node (ref "JP2") (pin "3") (pinfunction "3_3") (pintype "passive"))
    )
    (net (code "41") (name "Net-(IC3B-I1)") (class "Default")
      (node (ref "IC3") (pin "5") (pinfunction "I1_5") (pintype "input"))
      (node (ref "IC6") (pin "1") (pinfunction "I0_1") (pintype "input"))
      (node (ref "IC8") (pin "16") (pinfunction "7Q_16") (pintype "tri_state"))
      (node (ref "JP2") (pin "7") (pinfunction "7_7") (pintype "passive"))
    )
    (net (code "42") (name "Net-(IC3B-O)") (class "Default")
      (node (ref "IC3") (pin "6") (pinfunction "O_6") (pintype "output"))
      (node (ref "IC6") (pin "13") (pinfunction "I1_13") (pintype "input"))
    )
    (net (code "43") (name "Net-(IC3C-I1)") (class "Default")
      (node (ref "IC3") (pin "10") (pinfunction "I1_10") (pintype "input"))
      (node (ref "IC8") (pin "5") (pinfunction "2Q_5") (pintype "tri_state"))
      (node (ref "JP2") (pin "2") (pinfunction "2_2") (pintype "passive"))
    )
    (net (code "44") (name "Net-(IC3C-O)") (class "Default")
      (node (ref "IC3") (pin "8") (pinfunction "O_8") (pintype "output"))
      (node (ref "IC6") (pin "10") (pinfunction "I1_10") (pintype "input"))
    )
    (net (code "45") (name "Net-(IC3D-I0)") (class "Default")
      (node (ref "IC3") (pin "12") (pinfunction "I0_12") (pintype "input"))
      (node (ref "IC6") (pin "2") (pinfunction "I1_2") (pintype "input"))
      (node (ref "IC8") (pin "19") (pinfunction "8Q_19") (pintype "tri_state"))
      (node (ref "JP2") (pin "8") (pinfunction "8_8") (pintype "passive"))
    )
    (net (code "46") (name "Net-(IC3D-I1)") (class "Default")
      (node (ref "IC3") (pin "13") (pinfunction "I1_13") (pintype "input"))
      (node (ref "IC8") (pin "9") (pinfunction "4Q_9") (pintype "tri_state"))
      (node (ref "JP2") (pin "4") (pinfunction "4_4") (pintype "passive"))
    )
    (net (code "47") (name "Net-(IC3D-O)") (class "Default")
      (node (ref "IC3") (pin "11") (pinfunction "O_11") (pintype "output"))
      (node (ref "IC6") (pin "12") (pinfunction "I0_12") (pintype "input"))
      (node (ref "IC6") (pin "9") (pinfunction "I0_9") (pintype "input"))
    )
    (net (code "48") (name "Net-(IC4A-D)") (class "Default")
      (node (ref "IC4") (pin "2") (pinfunction "D_2") (pintype "input"))
      (node (ref "IC5") (pin "13") (pinfunction "I1_13") (pintype "input"))
      (node (ref "IC7") (pin "2") (pinfunction "O_2") (pintype "output"))
      (node (ref "IC7") (pin "5") (pinfunction "I_5") (pintype "input"))
    )
    (net (code "49") (name "Net-(IC4A-Q)") (class "Default")
      (node (ref "IC4") (pin "5") (pinfunction "Q_5") (pintype "output"))
      (node (ref "IC5") (pin "12") (pinfunction "I0_12") (pintype "input"))
    )
    (net (code "50") (name "Net-(IC4B-D)") (class "Default")
      (node (ref "IC4") (pin "12") (pinfunction "D_12") (pintype "input"))
      (node (ref "IC5") (pin "11") (pinfunction "O_11") (pintype "output"))
    )
    (net (code "51") (name "Net-(IC4B-Q)") (class "Default")
      (node (ref "IC4") (pin "9") (pinfunction "Q_9") (pintype "output"))
      (node (ref "IC5") (pin "4") (pinfunction "I0_4") (pintype "input"))
    )
    (net (code "52") (name "Net-(IC5C-I0)") (class "Default")
      (node (ref "IC5") (pin "9") (pinfunction "I0_9") (pintype "input"))
      (node (ref "IC7") (pin "1") (pinfunction "I_1") (pintype "input"))
      (node (ref "IC9") (pin "3") (pinfunction "O_3") (pintype "output"))
    )
    (net (code "53") (name "Net-(IC5C-I1)") (class "Default")
      (node (ref "IC5") (pin "10") (pinfunction "I1_10") (pintype "input"))
      (node (ref "IC7") (pin "12") (pinfunction "O_12") (pintype "output"))
    )
    (net (code "54") (name "Net-(IC5C-O)") (class "Default")
      (node (ref "IC5") (pin "8") (pinfunction "O_8") (pintype "output"))
      (node (ref "IC8") (pin "11") (pinfunction "ENC_11") (pintype "input"))
    )
    (net (code "55") (name "Net-(IC6A-O)") (class "Default")
      (node (ref "IC6") (pin "3") (pinfunction "O_3") (pintype "output"))
      (node (ref "IC6") (pin "5") (pinfunction "I1_5") (pintype "input"))
    )
    (net (code "56") (name "Net-(IC7A-I)") (class "Default")
      (node (ref "IC7") (pin "13") (pinfunction "I_13") (pintype "input"))
      (node (ref "IC7") (pin "6") (pinfunction "O_6") (pintype "output"))
    )
    (net (code "57") (name "Net-(IC7C-I)") (class "Default")
      (node (ref "C24") (pin "1") (pinfunction "1_1") (pintype "passive"))
      (node (ref "IC7") (pin "9") (pinfunction "I_9") (pintype "input"))
      (node (ref "R27") (pin "2") (pinfunction "2_2") (pintype "passive"))
    )
    (net (code "58") (name "Net-(IC8A-1Q)") (class "Default")
      (node (ref "IC8") (pin "2") (pinfunction "1Q_2") (pintype "tri_state"))
      (node (ref "JP2") (pin "1") (pinfunction "1_1") (pintype "passive"))
    )
    (net (code "59") (name "Net-(IC9A-I0)") (class "Default")
      (node (ref "IC9") (pin "1") (pinfunction "I0_1") (pintype "input"))
      (node (ref "IC9") (pin "6") (pinfunction "O_6") (pintype "output"))
    )
    (net (code "60") (name "Net-(IC9A-I1)") (class "Default")
      (node (ref "IC9") (pin "2") (pinfunction "I1_2") (pintype "input"))
      (node (ref "IC9") (pin "8") (pinfunction "O_8") (pintype "output"))
    )
    (net (code "61") (name "Net-(IC9B-I0)") (class "Default")
      (node (ref "IC9") (pin "11") (pinfunction "O_11") (pintype "output"))
      (node (ref "IC9") (pin "4") (pinfunction "I0_4") (pintype "input"))
    )
    (net (code "62") (name "Net-(IC10B-I0)") (class "Default")
      (node (ref "IC10") (pin "4") (pinfunction "I0_4") (pintype "input"))
      (node (ref "IC11") (pin "4") (pinfunction "O_4") (pintype "output"))
      (node (ref "IC8") (pin "13") (pinfunction "5D_13") (pintype "input"))
    )
    (net (code "63") (name "Net-(IC10B-I1)") (class "Default")
      (node (ref "IC10") (pin "5") (pinfunction "I1_5") (pintype "input"))
      (node (ref "IC11") (pin "6") (pinfunction "O_6") (pintype "output"))
      (node (ref "IC8") (pin "14") (pinfunction "6D_14") (pintype "input"))
    )
    (net (code "64") (name "Net-(IC10B-O)") (class "Default")
      (node (ref "IC10") (pin "6") (pinfunction "O_6") (pintype "output"))
      (node (ref "IC9") (pin "9") (pinfunction "I0_9") (pintype "input"))
    )
    (net (code "65") (name "Net-(IC10C-I0)") (class "Default")
      (node (ref "IC10") (pin "9") (pinfunction "I0_9") (pintype "input"))
      (node (ref "IC12") (pin "12") (pinfunction "O_12") (pintype "output"))
      (node (ref "IC8") (pin "17") (pinfunction "7D_17") (pintype "input"))
    )
    (net (code "66") (name "Net-(IC10C-I1)") (class "Default")
      (node (ref "IC10") (pin "10") (pinfunction "I1_10") (pintype "input"))
      (node (ref "IC12") (pin "10") (pinfunction "O_10") (pintype "output"))
      (node (ref "IC8") (pin "18") (pinfunction "8D_18") (pintype "input"))
    )
    (net (code "67") (name "Net-(IC10C-O)") (class "Default")
      (node (ref "IC10") (pin "8") (pinfunction "O_8") (pintype "output"))
      (node (ref "IC9") (pin "10") (pinfunction "I1_10") (pintype "input"))
    )
    (net (code "68") (name "Net-(IC10D-I0)") (class "Default")
      (node (ref "IC10") (pin "12") (pinfunction "I0_12") (pintype "input"))
      (node (ref "IC11") (pin "8") (pinfunction "O_8") (pintype "output"))
      (node (ref "IC8") (pin "7") (pinfunction "3D_7") (pintype "input"))
    )
    (net (code "69") (name "Net-(IC10D-I1)") (class "Default")
      (node (ref "IC10") (pin "13") (pinfunction "I1_13") (pintype "input"))
      (node (ref "IC11") (pin "2") (pinfunction "O_2") (pintype "output"))
      (node (ref "IC8") (pin "8") (pinfunction "4D_8") (pintype "input"))
    )
    (net (code "70") (name "Net-(IC10D-O)") (class "Default")
      (node (ref "IC10") (pin "11") (pinfunction "O_11") (pintype "output"))
      (node (ref "IC9") (pin "5") (pinfunction "I1_5") (pintype "input"))
    )
    (net (code "71") (name "Net-(IC11A-I)") (class "Default")
      (node (ref "C2") (pin "1") (pinfunction "1_1") (pintype "passive"))
      (node (ref "IC11") (pin "13") (pinfunction "I_13") (pintype "input"))
      (node (ref "R6") (pin "2") (pinfunction "2_2") (pintype "passive"))
    )
    (net (code "72") (name "Net-(IC11A-O)") (class "Default")
      (node (ref "IC11") (pin "12") (pinfunction "O_12") (pintype "output"))
      (node (ref "IC8") (pin "3") (pinfunction "1D_3") (pintype "input"))
      (node (ref "IC9") (pin "12") (pinfunction "I0_12") (pintype "input"))
    )
    (net (code "73") (name "Net-(IC11B-I)") (class "Default")
      (node (ref "C3") (pin "1") (pinfunction "1_1") (pintype "passive"))
      (node (ref "IC11") (pin "11") (pinfunction "I_11") (pintype "input"))
      (node (ref "R8") (pin "2") (pinfunction "2_2") (pintype "passive"))
    )
    (net (code "74") (name "Net-(IC11B-O)") (class "Default")
      (node (ref "IC11") (pin "10") (pinfunction "O_10") (pintype "output"))
      (node (ref "IC8") (pin "4") (pinfunction "2D_4") (pintype "input"))
      (node (ref "IC9") (pin "13") (pinfunction "I1_13") (pintype "input"))
    )
    (net (code "75") (name "Net-(IC11C-I)") (class "Default")
      (node (ref "C4") (pin "1") (pinfunction "1_1") (pintype "passive"))
      (node (ref "IC11") (pin "9") (pinfunction "I_9") (pintype "input"))
      (node (ref "R10") (pin "2") (pinfunction "2_2") (pintype "passive"))
    )
    (net (code "76") (name "Net-(IC11D-I)") (class "Default")
      (node (ref "C5") (pin "1") (pinfunction "1_1") (pintype "passive"))
      (node (ref "IC11") (pin "1") (pinfunction "I_1") (pintype "input"))
      (node (ref "R12") (pin "2") (pinfunction "2_2") (pintype "passive"))
    )
    (net (code "77") (name "Net-(IC11E-I)") (class "Default")
      (node (ref "C6") (pin "1") (pinfunction "1_1") (pintype "passive"))
      (node (ref "IC11") (pin "3") (pinfunction "I_3") (pintype "input"))
      (node (ref "R14") (pin "2") (pinfunction "2_2") (pintype "passive"))
    )
    (net (code "78") (name "Net-(IC11F-I)") (class "Default")
      (node (ref "C7") (pin "1") (pinfunction "1_1") (pintype "passive"))
      (node (ref "IC11") (pin "5") (pinfunction "I_5") (pintype "input"))
      (node (ref "R16") (pin "2") (pinfunction "2_2") (pintype "passive"))
    )
    (net (code "79") (name "Net-(IC12A-I)") (class "Default")
      (node (ref "C8") (pin "1") (pinfunction "1_1") (pintype "passive"))
      (node (ref "IC12") (pin "13") (pinfunction "I_13") (pintype "input"))
      (node (ref "R18") (pin "2") (pinfunction "2_2") (pintype "passive"))
    )
    (net (code "80") (name "Net-(IC12B-I)") (class "Default")
      (node (ref "C9") (pin "1") (pinfunction "1_1") (pintype "passive"))
      (node (ref "IC12") (pin "11") (pinfunction "I_11") (pintype "input"))
      (node (ref "R20") (pin "2") (pinfunction "2_2") (pintype "passive"))
    )
    (net (code "81") (name "Net-(IC12C-I)") (class "Default")
      (node (ref "C12") (pin "1") (pinfunction "1_1") (pintype "passive"))
      (node (ref "IC12") (pin "9") (pinfunction "I_9") (pintype "input"))
      (node (ref "R26") (pin "2") (pinfunction "2_2") (pintype "passive"))
    )
    (net (code "82") (name "Net-(IC12D-I)") (class "Default")
      (node (ref "C11") (pin "1") (pinfunction "1_1") (pintype "passive"))
      (node (ref "IC12") (pin "1") (pinfunction "I_1") (pintype "input"))
      (node (ref "R24") (pin "2") (pinfunction "2_2") (pintype "passive"))
    )
    (net (code "83") (name "Net-(IC12E-I)") (class "Default")
      (node (ref "C1") (pin "1") (pinfunction "1_1") (pintype "passive"))
      (node (ref "IC12") (pin "3") (pinfunction "I_3") (pintype "input"))
      (node (ref "R4") (pin "2") (pinfunction "2_2") (pintype "passive"))
    )
    (net (code "84") (name "Net-(IC12F-I)") (class "Default")
      (node (ref "C10") (pin "1") (pinfunction "1_1") (pintype "passive"))
      (node (ref "IC12") (pin "5") (pinfunction "I_5") (pintype "input"))
      (node (ref "R22") (pin "2") (pinfunction "2_2") (pintype "passive"))
    )
    (net (code "85") (name "Net-(LED1-C)") (class "Default")
      (node (ref "LED1") (pin "K") (pinfunction "C_K") (pintype "passive"))
      (node (ref "R30") (pin "2") (pinfunction "2_2") (pintype "passive"))
    )
    (net (code "86") (name "Net-(LED2-C)") (class "Default")
      (node (ref "LED2") (pin "K") (pinfunction "C_K") (pintype "passive"))
      (node (ref "R29") (pin "2") (pinfunction "2_2") (pintype "passive"))
    )
    (net (code "87") (name "Net-(LED3-C)") (class "Default")
      (node (ref "LED3") (pin "K") (pinfunction "C_K") (pintype "passive"))
      (node (ref "R31") (pin "2") (pinfunction "2_2") (pintype "passive"))
    )
    (net (code "88") (name "Net-(LED4-C)") (class "Default")
      (node (ref "LED4") (pin "K") (pinfunction "C_K") (pintype "passive"))
      (node (ref "R32") (pin "2") (pinfunction "2_2") (pintype "passive"))
    )
    (net (code "89") (name "Net-(LED5-C)") (class "Default")
      (node (ref "LED5") (pin "K") (pinfunction "C_K") (pintype "passive"))
      (node (ref "R33") (pin "2") (pinfunction "2_2") (pintype "passive"))
    )
    (net (code "90") (name "Net-(LED6-C)") (class "Default")
      (node (ref "LED6") (pin "K") (pinfunction "C_K") (pintype "passive"))
      (node (ref "R34") (pin "2") (pinfunction "2_2") (pintype "passive"))
    )
    (net (code "91") (name "Net-(LED10-C)") (class "Default")
      (node (ref "LED10") (pin "K") (pinfunction "C_K") (pintype "passive"))
      (node (ref "R39") (pin "2") (pinfunction "2_2") (pintype "passive"))
    )
    (net (code "92") (name "Net-(LED11-C)") (class "Default")
      (node (ref "LED11") (pin "K") (pinfunction "C_K") (pintype "passive"))
      (node (ref "R48") (pin "1") (pinfunction "1_1") (pintype "passive"))
    )
    (net (code "93") (name "Net-(LED12-C)") (class "Default")
      (node (ref "LED12") (pin "K") (pinfunction "C_K") (pintype "passive"))
      (node (ref "R40") (pin "2") (pinfunction "2_2") (pintype "passive"))
    )
    (net (code "94") (name "Net-(LED13-C)") (class "Default")
      (node (ref "LED13") (pin "K") (pinfunction "C_K") (pintype "passive"))
      (node (ref "R41") (pin "2") (pinfunction "2_2") (pintype "passive"))
    )
    (net (code "95") (name "Net-(LED14-C)") (class "Default")
      (node (ref "LED14") (pin "K") (pinfunction "C_K") (pintype "passive"))
      (node (ref "R42") (pin "2") (pinfunction "2_2") (pintype "passive"))
    )
    (net (code "96") (name "Net-(LED15-C)") (class "Default")
      (node (ref "LED15") (pin "K") (pinfunction "C_K") (pintype "passive"))
      (node (ref "R43") (pin "2") (pinfunction "2_2") (pintype "passive"))
    )
    (net (code "97") (name "Net-(LED16-C)") (class "Default")
      (node (ref "LED16") (pin "K") (pinfunction "C_K") (pintype "passive"))
      (node (ref "R44") (pin "2") (pinfunction "2_2") (pintype "passive"))
    )
    (net (code "98") (name "Net-(LED17-C)") (class "Default")
      (node (ref "LED17") (pin "K") (pinfunction "C_K") (pintype "passive"))
      (node (ref "R45") (pin "2") (pinfunction "2_2") (pintype "passive"))
    )
    (net (code "99") (name "Net-(LED18-C)") (class "Default")
      (node (ref "LED18") (pin "K") (pinfunction "C_K") (pintype "passive"))
      (node (ref "R46") (pin "2") (pinfunction "2_2") (pintype "passive"))
    )
    (net (code "100") (name "Net-(LED19-C)") (class "Default")
      (node (ref "LED19") (pin "K") (pinfunction "C_K") (pintype "passive"))
      (node (ref "R47") (pin "1") (pinfunction "1_1") (pintype "passive"))
    )
    (net (code "101") (name "Net-(LED20-C)") (class "Default")
      (node (ref "LED20") (pin "K") (pinfunction "C_K") (pintype "passive"))
      (node (ref "R38") (pin "1") (pinfunction "1_1") (pintype "passive"))
    )
    (net (code "102") (name "Net-(S2-S)") (class "Default")
      (node (ref "R3") (pin "1") (pinfunction "1_1") (pintype "passive"))
      (node (ref "R4") (pin "1") (pinfunction "1_1") (pintype "passive"))
      (node (ref "S2") (pin "1") (pinfunction "S_1") (pintype "passive"))
      (node (ref "S2") (pin "2") (pinfunction "S1_2") (pintype "passive"))
    )
    (net (code "103") (name "Net-(S3-S)") (class "Default")
      (node (ref "R5") (pin "1") (pinfunction "1_1") (pintype "passive"))
      (node (ref "R6") (pin "1") (pinfunction "1_1") (pintype "passive"))
      (node (ref "S3") (pin "1") (pinfunction "S_1") (pintype "passive"))
      (node (ref "S3") (pin "2") (pinfunction "S1_2") (pintype "passive"))
    )
    (net (code "104") (name "Net-(S4-S)") (class "Default")
      (node (ref "R7") (pin "1") (pinfunction "1_1") (pintype "passive"))
      (node (ref "R8") (pin "1") (pinfunction "1_1") (pintype "passive"))
      (node (ref "S4") (pin "1") (pinfunction "S_1") (pintype "passive"))
      (node (ref "S4") (pin "2") (pinfunction "S1_2") (pintype "passive"))
    )
    (net (code "105") (name "Net-(S5-S)") (class "Default")
      (node (ref "R10") (pin "1") (pinfunction "1_1") (pintype "passive"))
      (node (ref "R9") (pin "1") (pinfunction "1_1") (pintype "passive"))
      (node (ref "S5") (pin "1") (pinfunction "S_1") (pintype "passive"))
      (node (ref "S5") (pin "2") (pinfunction "S1_2") (pintype "passive"))
    )
    (net (code "106") (name "Net-(S6-S)") (class "Default")
      (node (ref "R11") (pin "1") (pinfunction "1_1") (pintype "passive"))
      (node (ref "R12") (pin "1") (pinfunction "1_1") (pintype "passive"))
      (node (ref "S6") (pin "1") (pinfunction "S_1") (pintype "passive"))
      (node (ref "S6") (pin "2") (pinfunction "S1_2") (pintype "passive"))
    )
    (net (code "107") (name "Net-(S7-S)") (class "Default")
      (node (ref "R13") (pin "1") (pinfunction "1_1") (pintype "passive"))
      (node (ref "R14") (pin "1") (pinfunction "1_1") (pintype "passive"))
      (node (ref "S7") (pin "1") (pinfunction "S_1") (pintype "passive"))
      (node (ref "S7") (pin "2") (pinfunction "S1_2") (pintype "passive"))
    )
    (net (code "108") (name "Net-(S8-S)") (class "Default")
      (node (ref "R15") (pin "1") (pinfunction "1_1") (pintype "passive"))
      (node (ref "R16") (pin "1") (pinfunction "1_1") (pintype "passive"))
      (node (ref "S8") (pin "1") (pinfunction "S_1") (pintype "passive"))
      (node (ref "S8") (pin "2") (pinfunction "S1_2") (pintype "passive"))
    )
    (net (code "109") (name "Net-(S9-S)") (class "Default")
      (node (ref "R17") (pin "1") (pinfunction "1_1") (pintype "passive"))
      (node (ref "R18") (pin "1") (pinfunction "1_1") (pintype "passive"))
      (node (ref "S9") (pin "1") (pinfunction "S_1") (pintype "passive"))
      (node (ref "S9") (pin "2") (pinfunction "S1_2") (pintype "passive"))
    )
    (net (code "110") (name "Net-(S10-S)") (class "Default")
      (node (ref "R19") (pin "1") (pinfunction "1_1") (pintype "passive"))
      (node (ref "R20") (pin "1") (pinfunction "1_1") (pintype "passive"))
      (node (ref "S10") (pin "1") (pinfunction "S_1") (pintype "passive"))
      (node (ref "S10") (pin "2") (pinfunction "S1_2") (pintype "passive"))
    )
    (net (code "111") (name "Net-(S11-S)") (class "Default")
      (node (ref "R21") (pin "1") (pinfunction "1_1") (pintype "passive"))
      (node (ref "R22") (pin "1") (pinfunction "1_1") (pintype "passive"))
      (node (ref "S11") (pin "1") (pinfunction "S_1") (pintype "passive"))
      (node (ref "S11") (pin "2") (pinfunction "S1_2") (pintype "passive"))
    )
    (net (code "112") (name "Net-(S12-S)") (class "Default")
      (node (ref "R23") (pin "1") (pinfunction "1_1") (pintype "passive"))
      (node (ref "R24") (pin "1") (pinfunction "1_1") (pintype "passive"))
      (node (ref "S12") (pin "1") (pinfunction "S_1") (pintype "passive"))
      (node (ref "S12") (pin "2") (pinfunction "S1_2") (pintype "passive"))
    )
    (net (code "113") (name "Net-(S13-S)") (class "Default")
      (node (ref "R25") (pin "1") (pinfunction "1_1") (pintype "passive"))
      (node (ref "R26") (pin "1") (pinfunction "1_1") (pintype "passive"))
      (node (ref "S13") (pin "1") (pinfunction "S_1") (pintype "passive"))
      (node (ref "S13") (pin "2") (pinfunction "S1_2") (pintype "passive"))
    )
    (net (code "114") (name "Net-(S14-S)") (class "Default")
      (node (ref "R2") (pin "1") (pinfunction "1_1") (pintype "passive"))
      (node (ref "R27") (pin "1") (pinfunction "1_1") (pintype "passive"))
      (node (ref "S14") (pin "1") (pinfunction "S_1") (pintype "passive"))
      (node (ref "S14") (pin "2") (pinfunction "S1_2") (pintype "passive"))
    )
    (net (code "115") (name "VCC") (class "Default")
      (node (ref "C1") (pin "2") (pinfunction "2_2") (pintype "passive"))
      (node (ref "C10") (pin "2") (pinfunction "2_2") (pintype "passive"))
      (node (ref "C11") (pin "2") (pinfunction "2_2") (pintype "passive"))
      (node (ref "C12") (pin "2") (pinfunction "2_2") (pintype "passive"))
      (node (ref "C13") (pin "1") (pinfunction "1_1") (pintype "passive"))
      (node (ref "C14") (pin "1") (pinfunction "1_1") (pintype "passive"))
      (node (ref "C15") (pin "1") (pinfunction "1_1") (pintype "passive"))
      (node (ref "C16") (pin "1") (pinfunction "1_1") (pintype "passive"))
      (node (ref "C17") (pin "1") (pinfunction "1_1") (pintype "passive"))
      (node (ref "C18") (pin "1") (pinfunction "1_1") (pintype "passive"))
      (node (ref "C19") (pin "1") (pinfunction "1_1") (pintype "passive"))
      (node (ref "C20") (pin "1") (pinfunction "1_1") (pintype "passive"))
      (node (ref "C21") (pin "1") (pinfunction "1_1") (pintype "passive"))
      (node (ref "C22") (pin "1") (pinfunction "1_1") (pintype "passive"))
      (node (ref "C23") (pin "1") (pinfunction "1_1") (pintype "passive"))
      (node (ref "IC4") (pin "1") (pinfunction "CLR_1") (pintype "input"))
      (node (ref "IC4") (pin "10") (pinfunction "PRE_10") (pintype "input"))
      (node (ref "IC4") (pin "13") (pinfunction "CLR_13") (pintype "input"))
      (node (ref "IC4") (pin "4") (pinfunction "PRE_4") (pintype "input"))
      (node (ref "JP1") (pin "17") (pinfunction "17_17") (pintype "passive"))
      (node (ref "JP1") (pin "19") (pinfunction "19_19") (pintype "passive"))
      (node (ref "JP3") (pin "2") (pinfunction "2_2") (pintype "passive"))
      (node (ref "QG2") (pin "14") (pinfunction "VCC_14") (pintype "power_in"))
      (node (ref "R11") (pin "2") (pinfunction "2_2") (pintype "passive"))
      (node (ref "R13") (pin "2") (pinfunction "2_2") (pintype "passive"))
      (node (ref "R15") (pin "2") (pinfunction "2_2") (pintype "passive"))
      (node (ref "R17") (pin "2") (pinfunction "2_2") (pintype "passive"))
      (node (ref "R19") (pin "2") (pinfunction "2_2") (pintype "passive"))
      (node (ref "R2") (pin "2") (pinfunction "2_2") (pintype "passive"))
      (node (ref "R5") (pin "2") (pinfunction "2_2") (pintype "passive"))
      (node (ref "R7") (pin "2") (pinfunction "2_2") (pintype "passive"))
      (node (ref "R9") (pin "2") (pinfunction "2_2") (pintype "passive"))
      (node (ref "S11") (pin "3") (pinfunction "P_3") (pintype "passive"))
      (node (ref "S11") (pin "4") (pinfunction "P1_4") (pintype "passive"))
      (node (ref "S12") (pin "3") (pinfunction "P_3") (pintype "passive"))
      (node (ref "S12") (pin "4") (pinfunction "P1_4") (pintype "passive"))
      (node (ref "S13") (pin "3") (pinfunction "P_3") (pintype "passive"))
      (node (ref "S13") (pin "4") (pinfunction "P1_4") (pintype "passive"))
      (node (ref "S2") (pin "3") (pinfunction "P_3") (pintype "passive"))
      (node (ref "S2") (pin "4") (pinfunction "P1_4") (pintype "passive"))
    )
    (net (code "116") (name "unconnected-(IC4A-~{Q}-Pad6)") (class "Default")
      (node (ref "IC4") (pin "6") (pinfunction "~{Q}_6") (pintype "output"))
    )
    (net (code "117") (name "unconnected-(IC4B-~{Q}-Pad8)") (class "Default")
      (node (ref "IC4") (pin "8") (pinfunction "~{Q}_8") (pintype "output"))
    )
    (net (code "118") (name "unconnected-(IC5A-I0-Pad1)") (class "Default")
      (node (ref "IC5") (pin "1") (pinfunction "I0_1") (pintype "input"))
    )
    (net (code "119") (name "unconnected-(IC5A-I1-Pad2)") (class "Default")
      (node (ref "IC5") (pin "2") (pinfunction "I1_2") (pintype "input"))
    )
    (net (code "120") (name "unconnected-(IC5A-O-Pad3)") (class "Default")
      (node (ref "IC5") (pin "3") (pinfunction "O_3") (pintype "output"))
    )
    (net (code "121") (name "unconnected-(IC7B-I-Pad11)") (class "Default")
      (node (ref "IC7") (pin "11") (pinfunction "I_11") (pintype "input"))
    )
    (net (code "122") (name "unconnected-(IC7B-O-Pad10)") (class "Default")
      (node (ref "IC7") (pin "10") (pinfunction "O_10") (pintype "output"))
    )
    (net (code "123") (name "unconnected-(IC7E-I-Pad3)") (class "Default")
      (node (ref "IC7") (pin "3") (pinfunction "I_3") (pintype "input"))
    )
    (net (code "124") (name "unconnected-(IC7E-O-Pad4)") (class "Default")
      (node (ref "IC7") (pin "4") (pinfunction "O_4") (pintype "output"))
    )
    (net (code "125") (name "unconnected-(IC10A-I0-Pad1)") (class "Default")
      (node (ref "IC10") (pin "1") (pinfunction "I0_1") (pintype "input"))
    )
    (net (code "126") (name "unconnected-(IC10A-I1-Pad2)") (class "Default")
      (node (ref "IC10") (pin "2") (pinfunction "I1_2") (pintype "input"))
    )
    (net (code "127") (name "unconnected-(IC10A-O-Pad3)") (class "Default")
      (node (ref "IC10") (pin "3") (pinfunction "O_3") (pintype "output"))
    )
    (net (code "128") (name "unconnected-(IC13B-QA-Pad11)") (class "Default")
      (node (ref "IC13") (pin "11") (pinfunction "QA_11") (pintype "output"))
    )
    (net (code "129") (name "unconnected-(IC13B-QB-Pad10)") (class "Default")
      (node (ref "IC13") (pin "10") (pinfunction "QB_10") (pintype "output"))
    )
    (net (code "130") (name "unconnected-(IC13B-QC-Pad9)") (class "Default")
      (node (ref "IC13") (pin "9") (pinfunction "QC_9") (pintype "output"))
    )
    (net (code "131") (name "unconnected-(QG2-TS-Pad1)") (class "Default")
      (node (ref "QG2") (pin "1") (pinfunction "TS_1") (pintype "passive"))
    )
  )
)
